# MyAmpV2.net
KiCad netlist of a schematic drawn in EAGLE
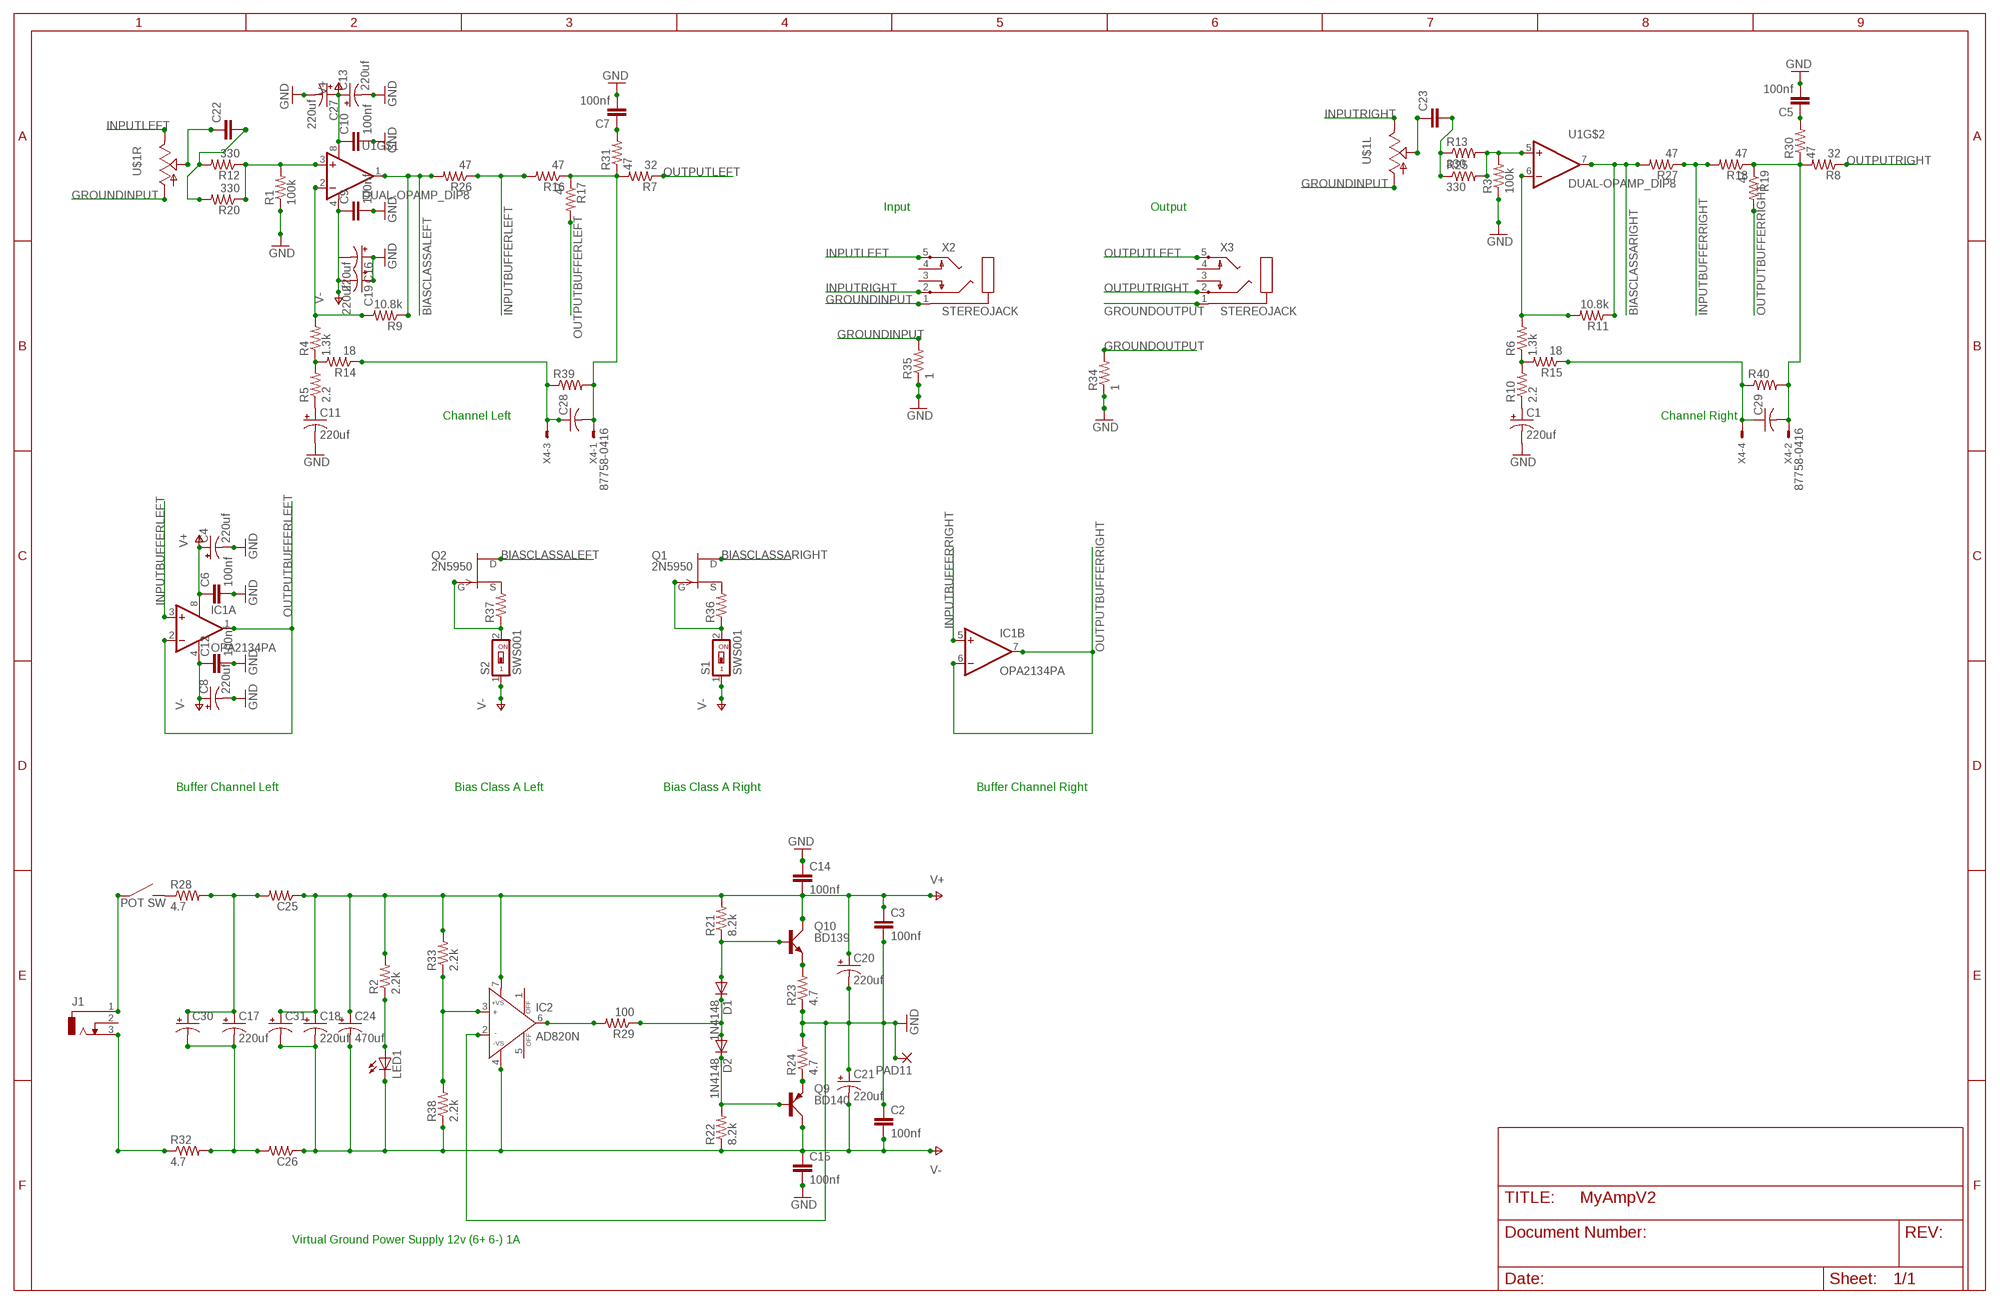
[diagram p0: schematic, sheet 1]

(export (version "E")
  (design (tool "Eeschema 10.0.6"))
  (components
    (comp (ref "C1")
      (value "220uf")
      (footprint "eagle-import:E5-10,5")
      (libsource (lib "eagle-import") (part "CPOL-USE5-10.5"))
    )
    (comp (ref "C2")
      (value "100nf")
      (footprint "eagle-import:C5B2.5")
      (libsource (lib "eagle-import") (part "C5/2.5"))
    )
    (comp (ref "C3")
      (value "100nf")
      (footprint "eagle-import:C5B2.5")
      (libsource (lib "eagle-import") (part "C5/2.5"))
    )
    (comp (ref "C4")
      (value "220uf")
      (footprint "eagle-import:E5-10,5")
      (libsource (lib "eagle-import") (part "CPOL-USE5-10.5"))
    )
    (comp (ref "C5")
      (value "100nf")
      (footprint "eagle-import:C5B2.5")
      (libsource (lib "eagle-import") (part "C5/2.5"))
    )
    (comp (ref "C6")
      (value "100nf")
      (footprint "eagle-import:C5B2.5")
      (libsource (lib "eagle-import") (part "C5/2.5"))
    )
    (comp (ref "C7")
      (value "100nf")
      (footprint "eagle-import:C5B2.5")
      (libsource (lib "eagle-import") (part "C5/2.5"))
    )
    (comp (ref "C8")
      (value "220uf")
      (footprint "eagle-import:E5-10,5")
      (libsource (lib "eagle-import") (part "CPOL-USE5-10.5"))
    )
    (comp (ref "C9")
      (value "100nf")
      (footprint "eagle-import:C5B2.5")
      (libsource (lib "eagle-import") (part "C5/2.5"))
    )
    (comp (ref "C10")
      (value "100nf")
      (footprint "eagle-import:C5B2.5")
      (libsource (lib "eagle-import") (part "C5/2.5"))
    )
    (comp (ref "C11")
      (value "220uf")
      (footprint "eagle-import:E5-10,5")
      (libsource (lib "eagle-import") (part "CPOL-USE5-10.5"))
    )
    (comp (ref "C12")
      (value "100nf")
      (footprint "eagle-import:C5B2.5")
      (libsource (lib "eagle-import") (part "C5/2.5"))
    )
    (comp (ref "C13")
      (value "220uf")
      (footprint "eagle-import:E5-10,5")
      (libsource (lib "eagle-import") (part "CPOL-USE5-10.5"))
    )
    (comp (ref "C14")
      (value "100nf")
      (footprint "eagle-import:C5B2.5")
      (libsource (lib "eagle-import") (part "C5/2.5"))
    )
    (comp (ref "C15")
      (value "100nf")
      (footprint "eagle-import:C5B2.5")
      (libsource (lib "eagle-import") (part "C5/2.5"))
    )
    (comp (ref "C16")
      (value "220uf")
      (footprint "eagle-import:E5-10,5")
      (libsource (lib "eagle-import") (part "CPOL-USE5-10.5"))
    )
    (comp (ref "C17")
      (value "220uf")
      (footprint "eagle-import:E5-10,5")
      (libsource (lib "eagle-import") (part "rcl_334_CPOL-USE5-10.5"))
    )
    (comp (ref "C18")
      (value "220uf")
      (footprint "eagle-import:E5-10,5")
      (libsource (lib "eagle-import") (part "rcl_334_CPOL-USE5-10.5"))
    )
    (comp (ref "C19")
      (value "220uf")
      (footprint "eagle-import:E5-10,5")
      (libsource (lib "eagle-import") (part "CPOL-USE5-10.5"))
    )
    (comp (ref "C20")
      (value "220uf")
      (footprint "eagle-import:D_7343-31R")
      (libsource (lib "eagle-import") (part "rcl_334_CPOL-USD/7343-31R"))
    )
    (comp (ref "C21")
      (value "220uf")
      (footprint "eagle-import:D_7343-31R")
      (libsource (lib "eagle-import") (part "rcl_334_CPOL-USD/7343-31R"))
    )
    (comp (ref "C22")
      (value "C22/6")
      (footprint "eagle-import:C22.5B6")
      (libsource (lib "eagle-import") (part "capacitor-wima_116_C22/6"))
    )
    (comp (ref "C23")
      (value "C22/6")
      (footprint "eagle-import:C22.5B6")
      (libsource (lib "eagle-import") (part "capacitor-wima_116_C22/6"))
    )
    (comp (ref "C24")
      (value "470uf")
      (footprint "eagle-import:E5-10,5")
      (libsource (lib "eagle-import") (part "CPOL-USE5-10.5"))
    )
    (comp (ref "C25")
      (value "R-US_0207/12")
      (footprint "eagle-import:0207_12")
      (libsource (lib "eagle-import") (part "resistor_348_R-US_0207/12"))
    )
    (comp (ref "C26")
      (value "R-US_0207/12")
      (footprint "eagle-import:0207_12")
      (libsource (lib "eagle-import") (part "resistor_348_R-US_0207/12"))
    )
    (comp (ref "C27")
      (value "220uf")
      (footprint "eagle-import:E5-10,5")
      (libsource (lib "eagle-import") (part "CPOL-USE5-10.5"))
    )
    (comp (ref "C28")
      (value "C-USC1206K")
      (footprint "eagle-import:C1206K")
      (libsource (lib "eagle-import") (part "C-USC1206K"))
    )
    (comp (ref "C29")
      (value "C-USC1206K")
      (footprint "eagle-import:C1206K")
      (libsource (lib "eagle-import") (part "C-USC1206K"))
    )
    (comp (ref "C30")
      (value "CPOL-USE7.5-16")
      (footprint "eagle-import:E7,5-16")
      (libsource (lib "eagle-import") (part "rcl_334_CPOL-USE7.5-16"))
    )
    (comp (ref "C31")
      (value "CPOL-USE7.5-16")
      (footprint "eagle-import:E7,5-16")
      (libsource (lib "eagle-import") (part "rcl_334_CPOL-USE7.5-16"))
    )
    (comp (ref "D1")
      (value "1N4148")
      (footprint "eagle-import:DO35-7")
      (libsource (lib "eagle-import") (part "1N4148DO35-7"))
    )
    (comp (ref "D2")
      (value "1N4148")
      (footprint "eagle-import:DO35-7")
      (libsource (lib "eagle-import") (part "1N4148DO35-7"))
    )
    (comp (ref "IC1")
      (value "OPA2134PA")
      (footprint "eagle-import:DIL08")
      (libsource (lib "eagle-import") (part "OPA2PA134"))
    )
    (comp (ref "IC2")
      (value "AD820N")
      (footprint "eagle-import:DIL08")
      (libsource (lib "eagle-import") (part "AD820N"))
    )
    (comp (ref "J1")
      (value "DCJ0303")
      (footprint "eagle-import:DCJ0303")
      (libsource (lib "eagle-import") (part "DCJ0303"))
    )
    (comp (ref "LED1")
      (value "LED3MM")
      (footprint "eagle-import:LED3MM")
      (libsource (lib "eagle-import") (part "LED3MM"))
    )
    (comp (ref "PAD11")
      (value "1,6/0,9")
      (footprint "eagle-import:1,6_0,9")
      (libsource (lib "eagle-import") (part "1,6/0,9"))
    )
    (comp (ref "Q1")
      (value "2N5950")
      (footprint "eagle-import:TO-92")
      (libsource (lib "eagle-import") (part "2N5950"))
    )
    (comp (ref "Q2")
      (value "2N5950")
      (footprint "eagle-import:TO-92")
      (libsource (lib "eagle-import") (part "2N5950"))
    )
    (comp (ref "Q9")
      (value "BD140")
      (footprint "eagle-import:TO126AV")
      (libsource (lib "eagle-import") (part "BD140"))
    )
    (comp (ref "Q10")
      (value "BD139")
      (footprint "eagle-import:TO126AV")
      (libsource (lib "eagle-import") (part "BD139"))
    )
    (comp (ref "R1")
      (value "100k")
      (footprint "eagle-import:0207_10")
      (libsource (lib "eagle-import") (part "R-US_0207/10"))
    )
    (comp (ref "R2")
      (value "2.2k")
      (footprint "eagle-import:0207_10")
      (libsource (lib "eagle-import") (part "resistor@1_R-US_0207/10"))
    )
    (comp (ref "R3")
      (value "100k")
      (footprint "eagle-import:0207_10")
      (libsource (lib "eagle-import") (part "R-US_0207/10"))
    )
    (comp (ref "R4")
      (value "1.3k")
      (footprint "eagle-import:0207_10")
      (libsource (lib "eagle-import") (part "R-US_0207/10"))
    )
    (comp (ref "R5")
      (value "2.2")
      (footprint "eagle-import:0204_5")
      (libsource (lib "eagle-import") (part "resistor_348_R-US_0204/5"))
    )
    (comp (ref "R6")
      (value "1.3k")
      (footprint "eagle-import:0207_10")
      (libsource (lib "eagle-import") (part "R-US_0207/10"))
    )
    (comp (ref "R7")
      (value "32")
      (footprint "eagle-import:0207_12")
      (libsource (lib "eagle-import") (part "resistor@1_R-US_0207/12"))
    )
    (comp (ref "R8")
      (value "32")
      (footprint "eagle-import:0207_12")
      (libsource (lib "eagle-import") (part "resistor@1_R-US_0207/12"))
    )
    (comp (ref "R9")
      (value "10.8k")
      (footprint "eagle-import:0207_10")
      (libsource (lib "eagle-import") (part "R-US_0207/10"))
    )
    (comp (ref "R10")
      (value "2.2")
      (footprint "eagle-import:0204_5")
      (libsource (lib "eagle-import") (part "resistor_348_R-US_0204/5"))
    )
    (comp (ref "R11")
      (value "10.8k")
      (footprint "eagle-import:0207_10")
      (libsource (lib "eagle-import") (part "R-US_0207/10"))
    )
    (comp (ref "R12")
      (value "330")
      (footprint "eagle-import:0207_10")
      (libsource (lib "eagle-import") (part "R-US_0207/10"))
    )
    (comp (ref "R13")
      (value "330")
      (footprint "eagle-import:0207_10")
      (libsource (lib "eagle-import") (part "R-US_0207/10"))
    )
    (comp (ref "R14")
      (value "18")
      (footprint "eagle-import:0207_12")
      (libsource (lib "eagle-import") (part "resistor@1_R-US_0207/12"))
    )
    (comp (ref "R15")
      (value "18")
      (footprint "eagle-import:0207_12")
      (libsource (lib "eagle-import") (part "resistor@1_R-US_0207/12"))
    )
    (comp (ref "R16")
      (value "47")
      (footprint "eagle-import:0207_12")
      (libsource (lib "eagle-import") (part "resistor@1_R-US_0207/12"))
    )
    (comp (ref "R17")
      (value "47")
      (footprint "eagle-import:0207_12")
      (libsource (lib "eagle-import") (part "resistor@1_R-US_0207/12"))
    )
    (comp (ref "R18")
      (value "47")
      (footprint "eagle-import:0207_12")
      (libsource (lib "eagle-import") (part "resistor@1_R-US_0207/12"))
    )
    (comp (ref "R19")
      (value "47")
      (footprint "eagle-import:0207_12")
      (libsource (lib "eagle-import") (part "resistor@1_R-US_0207/12"))
    )
    (comp (ref "R20")
      (value "330")
      (footprint "eagle-import:0207_10")
      (libsource (lib "eagle-import") (part "R-US_0207/10"))
    )
    (comp (ref "R21")
      (value "8.2k")
      (footprint "eagle-import:0207_10")
      (libsource (lib "eagle-import") (part "resistor@1_R-US_0207/10"))
    )
    (comp (ref "R22")
      (value "8.2k")
      (footprint "eagle-import:0207_10")
      (libsource (lib "eagle-import") (part "resistor@1_R-US_0207/10"))
    )
    (comp (ref "R23")
      (value "4.7")
      (footprint "eagle-import:0207_10")
      (libsource (lib "eagle-import") (part "resistor@1_R-US_0207/10"))
    )
    (comp (ref "R24")
      (value "4.7")
      (footprint "eagle-import:0207_10")
      (libsource (lib "eagle-import") (part "resistor@1_R-US_0207/10"))
    )
    (comp (ref "R25")
      (value "330")
      (footprint "eagle-import:0207_10")
      (libsource (lib "eagle-import") (part "R-US_0207/10"))
    )
    (comp (ref "R26")
      (value "47")
      (footprint "eagle-import:0207_10")
      (libsource (lib "eagle-import") (part "resistor@1_R-US_0207/10"))
    )
    (comp (ref "R27")
      (value "47")
      (footprint "eagle-import:0207_10")
      (libsource (lib "eagle-import") (part "resistor@1_R-US_0207/10"))
    )
    (comp (ref "R28")
      (value "4.7")
      (footprint "eagle-import:0207_10")
      (libsource (lib "eagle-import") (part "resistor@1_R-US_0207/10"))
    )
    (comp (ref "R29")
      (value "100")
      (footprint "eagle-import:0207_10")
      (libsource (lib "eagle-import") (part "resistor@1_R-US_0207/10"))
    )
    (comp (ref "R30")
      (value "47")
      (footprint "eagle-import:0207_7")
      (libsource (lib "eagle-import") (part "R-US_0207/7"))
    )
    (comp (ref "R31")
      (value "47")
      (footprint "eagle-import:0207_7")
      (libsource (lib "eagle-import") (part "R-US_0207/7"))
    )
    (comp (ref "R32")
      (value "4.7")
      (footprint "eagle-import:0207_10")
      (libsource (lib "eagle-import") (part "resistor@1_R-US_0207/10"))
    )
    (comp (ref "R33")
      (value "2.2k")
      (footprint "eagle-import:0207_10")
      (libsource (lib "eagle-import") (part "resistor@1_R-US_0207/10"))
    )
    (comp (ref "R34")
      (value "1")
      (footprint "eagle-import:0207_7")
      (libsource (lib "eagle-import") (part "R-US_0207/7"))
    )
    (comp (ref "R35")
      (value "1")
      (footprint "eagle-import:0207_7")
      (libsource (lib "eagle-import") (part "R-US_0207/7"))
    )
    (comp (ref "R36")
      (value "R-US_0204/5")
      (footprint "eagle-import:0204_5")
      (libsource (lib "eagle-import") (part "resistor@1_R-US_0204/5"))
    )
    (comp (ref "R37")
      (value "R-US_0204/5")
      (footprint "eagle-import:0204_5")
      (libsource (lib "eagle-import") (part "resistor@1_R-US_0204/5"))
    )
    (comp (ref "R38")
      (value "2.2k")
      (footprint "eagle-import:0207_10")
      (libsource (lib "eagle-import") (part "resistor@1_R-US_0207/10"))
    )
    (comp (ref "R39")
      (value "R-US_MELF0204W")
      (footprint "eagle-import:MINI_MELF-0204W")
      (libsource (lib "eagle-import") (part "resistor_348_R-US_MELF0204W"))
    )
    (comp (ref "R40")
      (value "R-US_MELF0204W")
      (footprint "eagle-import:MINI_MELF-0204W")
      (libsource (lib "eagle-import") (part "resistor_348_R-US_MELF0204W"))
    )
    (comp (ref "S1")
      (value "SWS001")
      (footprint "eagle-import:SMS-001")
      (libsource (lib "eagle-import") (part "SWS001"))
    )
    (comp (ref "S2")
      (value "SWS001")
      (footprint "eagle-import:SMS-001")
      (libsource (lib "eagle-import") (part "SWS001"))
    )
    (comp (ref "U$1")
      (value "ALPS_RK0971221Z05")
      (footprint "eagle-import:ALPS_RK0971221Z0X")
      (libsource (lib "eagle-import") (part "ALPS_RK0971221Z05"))
    )
    (comp (ref "U1")
      (value "DUAL-OPAMP_DIP8")
      (footprint "eagle-import:DIP-8")
      (libsource (lib "eagle-import") (part "DUAL-OPAMP_DIP8"))
    )
    (comp (ref "X2")
      (value "STEREOJACK")
      (footprint "eagle-import:STX3100")
      (libsource (lib "eagle-import") (part "STEREOJACK"))
    )
    (comp (ref "X3")
      (value "STEREOJACK")
      (footprint "eagle-import:STX3100")
      (libsource (lib "eagle-import") (part "STEREOJACK"))
    )
    (comp (ref "X4")
      (value "87758-0416")
      (footprint "eagle-import:87758-0416")
      (fields (field (name "MF") "FARNELL"))
      (libsource (lib "eagle-import") (part "87758-0416"))
    )
  )
  (nets
    (net (code "1") (name "/BIASCLASSALEFT") (class "Default")
      (node (ref "Q2") (pin "3") (pinfunction "D_3") (pintype "passive"))
      (node (ref "R26") (pin "2") (pinfunction "2_2") (pintype "passive"))
      (node (ref "R9") (pin "1") (pinfunction "1_1") (pintype "passive"))
      (node (ref "U1") (pin "1") (pinfunction "OUT_1") (pintype "output"))
    )
    (net (code "2") (name "/BIASCLASSARIGHT") (class "Default")
      (node (ref "Q1") (pin "3") (pinfunction "D_3") (pintype "passive"))
      (node (ref "R11") (pin "1") (pinfunction "1_1") (pintype "passive"))
      (node (ref "R27") (pin "2") (pinfunction "2_2") (pintype "passive"))
      (node (ref "U1") (pin "7") (pinfunction "OUT_7") (pintype "output"))
    )
    (net (code "3") (name "/GROUNDINPUT") (class "Default")
      (node (ref "R35") (pin "2") (pinfunction "2_2") (pintype "passive"))
      (node (ref "U$1") (pin "G1") (pinfunction "1_G1") (pintype "passive"))
      (node (ref "U$1") (pin "G2") (pinfunction "1_G2") (pintype "passive"))
      (node (ref "X2") (pin "1") (pinfunction "1_1") (pintype "passive"))
    )
    (net (code "4") (name "/GROUNDOUTPUT") (class "Default")
      (node (ref "R34") (pin "2") (pinfunction "2_2") (pintype "passive"))
      (node (ref "X3") (pin "1") (pinfunction "1_1") (pintype "passive"))
    )
    (net (code "5") (name "/INPUTBUFFERLEFT") (class "Default")
      (node (ref "IC1") (pin "3") (pinfunction "+IN_3") (pintype "input"))
      (node (ref "R16") (pin "2") (pinfunction "2_2") (pintype "passive"))
      (node (ref "R26") (pin "1") (pinfunction "1_1") (pintype "passive"))
    )
    (net (code "6") (name "/INPUTBUFFERRIGHT") (class "Default")
      (node (ref "IC1") (pin "5") (pinfunction "+IN_5") (pintype "input"))
      (node (ref "R18") (pin "2") (pinfunction "2_2") (pintype "passive"))
      (node (ref "R27") (pin "1") (pinfunction "1_1") (pintype "passive"))
    )
    (net (code "7") (name "/INPUTLEFT") (class "Default")
      (node (ref "U$1") (pin "I2") (pinfunction "3_I2") (pintype "passive"))
      (node (ref "X2") (pin "5") (pinfunction "5_5") (pintype "passive"))
    )
    (net (code "8") (name "/INPUTRIGHT") (class "Default")
      (node (ref "U$1") (pin "I1") (pinfunction "3_I1") (pintype "passive"))
      (node (ref "X2") (pin "2") (pinfunction "2_2") (pintype "passive"))
    )
    (net (code "9") (name "/OUTPUTBUFFERLEFT") (class "Default")
      (node (ref "IC1") (pin "1") (pinfunction "OUT_1") (pintype "output"))
      (node (ref "IC1") (pin "2") (pinfunction "-IN_2") (pintype "input"))
      (node (ref "R17") (pin "2") (pinfunction "2_2") (pintype "passive"))
    )
    (net (code "10") (name "/OUTPUTBUFFERRIGHT") (class "Default")
      (node (ref "IC1") (pin "6") (pinfunction "-IN_6") (pintype "input"))
      (node (ref "IC1") (pin "7") (pinfunction "OUT_7") (pintype "output"))
      (node (ref "R19") (pin "2") (pinfunction "2_2") (pintype "passive"))
    )
    (net (code "11") (name "/OUTPUTLEFT") (class "Default")
      (node (ref "R7") (pin "1") (pinfunction "1_1") (pintype "passive"))
      (node (ref "X3") (pin "5") (pinfunction "5_5") (pintype "passive"))
    )
    (net (code "12") (name "/OUTPUTRIGHT") (class "Default")
      (node (ref "R8") (pin "1") (pinfunction "1_1") (pintype "passive"))
      (node (ref "X3") (pin "2") (pinfunction "2_2") (pintype "passive"))
    )
    (net (code "13") (name "GND") (class "Default")
      (node (ref "C1") (pin "-") (pinfunction "-_-") (pintype "passive"))
      (node (ref "C10") (pin "2") (pinfunction "2_2") (pintype "passive"))
      (node (ref "C11") (pin "-") (pinfunction "-_-") (pintype "passive"))
      (node (ref "C12") (pin "2") (pinfunction "2_2") (pintype "passive"))
      (node (ref "C13") (pin "-") (pinfunction "-_-") (pintype "passive"))
      (node (ref "C14") (pin "1") (pinfunction "1_1") (pintype "passive"))
      (node (ref "C15") (pin "2") (pinfunction "2_2") (pintype "passive"))
      (node (ref "C16") (pin "+") (pinfunction "+_+") (pintype "passive"))
      (node (ref "C19") (pin "+") (pinfunction "+_+") (pintype "passive"))
      (node (ref "C2") (pin "1") (pinfunction "1_1") (pintype "passive"))
      (node (ref "C20") (pin "-") (pinfunction "-_-") (pintype "passive"))
      (node (ref "C21") (pin "+") (pinfunction "+_+") (pintype "passive"))
      (node (ref "C27") (pin "-") (pinfunction "-_-") (pintype "passive"))
      (node (ref "C3") (pin "2") (pinfunction "2_2") (pintype "passive"))
      (node (ref "C4") (pin "-") (pinfunction "-_-") (pintype "passive"))
      (node (ref "C5") (pin "2") (pinfunction "2_2") (pintype "passive"))
      (node (ref "C6") (pin "2") (pinfunction "2_2") (pintype "passive"))
      (node (ref "C7") (pin "2") (pinfunction "2_2") (pintype "passive"))
      (node (ref "C8") (pin "-") (pinfunction "-_-") (pintype "passive"))
      (node (ref "C9") (pin "2") (pinfunction "2_2") (pintype "passive"))
      (node (ref "IC2") (pin "2") (pinfunction "IN-_2") (pintype "input"))
      (node (ref "PAD11") (pin "1") (pinfunction "P_1") (pintype "passive"))
      (node (ref "R1") (pin "1") (pinfunction "1_1") (pintype "passive"))
      (node (ref "R23") (pin "1") (pinfunction "1_1") (pintype "passive"))
      (node (ref "R24") (pin "2") (pinfunction "2_2") (pintype "passive"))
      (node (ref "R3") (pin "1") (pinfunction "1_1") (pintype "passive"))
      (node (ref "R34") (pin "1") (pinfunction "1_1") (pintype "passive"))
      (node (ref "R35") (pin "1") (pinfunction "1_1") (pintype "passive"))
    )
    (net (code "14") (name "Net-(C1-Pad+)") (class "Default")
      (node (ref "C1") (pin "+") (pinfunction "+_+") (pintype "passive"))
      (node (ref "R10") (pin "1") (pinfunction "1_1") (pintype "passive"))
    )
    (net (code "15") (name "Net-(C5-Pad1)") (class "Default")
      (node (ref "C5") (pin "1") (pinfunction "1_1") (pintype "passive"))
      (node (ref "R30") (pin "2") (pinfunction "2_2") (pintype "passive"))
    )
    (net (code "16") (name "Net-(C7-Pad1)") (class "Default")
      (node (ref "C7") (pin "1") (pinfunction "1_1") (pintype "passive"))
      (node (ref "R31") (pin "2") (pinfunction "2_2") (pintype "passive"))
    )
    (net (code "17") (name "Net-(C11-Pad+)") (class "Default")
      (node (ref "C11") (pin "+") (pinfunction "+_+") (pintype "passive"))
      (node (ref "R5") (pin "1") (pinfunction "1_1") (pintype "passive"))
    )
    (net (code "18") (name "Net-(C17-Pad+)") (class "Default")
      (node (ref "C17") (pin "+") (pinfunction "+_+") (pintype "passive"))
      (node (ref "C25") (pin "2") (pinfunction "2_2") (pintype "passive"))
      (node (ref "C30") (pin "+") (pinfunction "+_+") (pintype "passive"))
      (node (ref "R28") (pin "2") (pinfunction "2_2") (pintype "passive"))
    )
    (net (code "19") (name "Net-(C17-Pad-)") (class "Default")
      (node (ref "C17") (pin "-") (pinfunction "-_-") (pintype "passive"))
      (node (ref "C26") (pin "2") (pinfunction "2_2") (pintype "passive"))
      (node (ref "C30") (pin "-") (pinfunction "-_-") (pintype "passive"))
      (node (ref "R32") (pin "2") (pinfunction "2_2") (pintype "passive"))
    )
    (net (code "20") (name "Net-(C22-Pad2)") (class "Default")
      (node (ref "C22") (pin "2") (pinfunction "2_2") (pintype "passive"))
      (node (ref "R12") (pin "2") (pinfunction "2_2") (pintype "passive"))
      (node (ref "R20") (pin "2") (pinfunction "2_2") (pintype "passive"))
    )
    (net (code "21") (name "Net-(C23-Pad2)") (class "Default")
      (node (ref "C23") (pin "2") (pinfunction "2_2") (pintype "passive"))
      (node (ref "R13") (pin "1") (pinfunction "1_1") (pintype "passive"))
      (node (ref "R25") (pin "1") (pinfunction "1_1") (pintype "passive"))
    )
    (net (code "22") (name "Net-(D1-PadA)") (class "Default")
      (node (ref "D1") (pin "A") (pinfunction "A_A") (pintype "passive"))
      (node (ref "Q10") (pin "B") (pinfunction "B_B") (pintype "passive"))
      (node (ref "R21") (pin "1") (pinfunction "1_1") (pintype "passive"))
    )
    (net (code "23") (name "Net-(D1-PadC)") (class "Default")
      (node (ref "D1") (pin "C") (pinfunction "C_C") (pintype "passive"))
      (node (ref "D2") (pin "A") (pinfunction "A_A") (pintype "passive"))
      (node (ref "R29") (pin "1") (pinfunction "1_1") (pintype "passive"))
    )
    (net (code "24") (name "Net-(D2-PadC)") (class "Default")
      (node (ref "D2") (pin "C") (pinfunction "C_C") (pintype "passive"))
      (node (ref "Q9") (pin "B") (pinfunction "B_B") (pintype "passive"))
      (node (ref "R22") (pin "2") (pinfunction "2_2") (pintype "passive"))
    )
    (net (code "25") (name "Net-(IC2-IN+)") (class "Default")
      (node (ref "IC2") (pin "3") (pinfunction "IN+_3") (pintype "input"))
      (node (ref "R33") (pin "1") (pinfunction "1_1") (pintype "passive"))
      (node (ref "R38") (pin "2") (pinfunction "2_2") (pintype "passive"))
    )
    (net (code "26") (name "Net-(IC2-OUT)") (class "Default")
      (node (ref "IC2") (pin "6") (pinfunction "OUT_6") (pintype "output"))
      (node (ref "R29") (pin "2") (pinfunction "2_2") (pintype "passive"))
    )
    (net (code "27") (name "Net-(J1-Pad1)") (class "Default")
      (node (ref "J1") (pin "1") (pinfunction "1_1") (pintype "passive"))
      (node (ref "U$1") (pin "S1") (pinfunction "S1_S1") (pintype "power_in"))
    )
    (net (code "28") (name "Net-(J1-Pad3)") (class "Default")
      (node (ref "J1") (pin "3") (pinfunction "3_3") (pintype "passive"))
      (node (ref "R32") (pin "1") (pinfunction "1_1") (pintype "passive"))
    )
    (net (code "29") (name "Net-(LED1-PadA)") (class "Default")
      (node (ref "LED1") (pin "A") (pinfunction "A_A") (pintype "passive"))
      (node (ref "R2") (pin "1") (pinfunction "1_1") (pintype "passive"))
    )
    (net (code "30") (name "Net-(Q1-G)") (class "Default")
      (node (ref "Q1") (pin "1") (pinfunction "G_1") (pintype "passive"))
      (node (ref "R36") (pin "1") (pinfunction "1_1") (pintype "passive"))
      (node (ref "S1") (pin "2") (pinfunction "2_2") (pintype "passive"))
    )
    (net (code "31") (name "Net-(Q1-S)") (class "Default")
      (node (ref "Q1") (pin "2") (pinfunction "S_2") (pintype "passive"))
      (node (ref "R36") (pin "2") (pinfunction "2_2") (pintype "passive"))
    )
    (net (code "32") (name "Net-(Q2-G)") (class "Default")
      (node (ref "Q2") (pin "1") (pinfunction "G_1") (pintype "passive"))
      (node (ref "R37") (pin "1") (pinfunction "1_1") (pintype "passive"))
      (node (ref "S2") (pin "2") (pinfunction "2_2") (pintype "passive"))
    )
    (net (code "33") (name "Net-(Q2-S)") (class "Default")
      (node (ref "Q2") (pin "2") (pinfunction "S_2") (pintype "passive"))
      (node (ref "R37") (pin "2") (pinfunction "2_2") (pintype "passive"))
    )
    (net (code "34") (name "Net-(Q9-PadE)") (class "Default")
      (node (ref "Q9") (pin "E") (pinfunction "E_E") (pintype "passive"))
      (node (ref "R24") (pin "1") (pinfunction "1_1") (pintype "passive"))
    )
    (net (code "35") (name "Net-(Q10-PadE)") (class "Default")
      (node (ref "Q10") (pin "E") (pinfunction "E_E") (pintype "passive"))
      (node (ref "R23") (pin "2") (pinfunction "2_2") (pintype "passive"))
    )
    (net (code "36") (name "Net-(R10-Pad2)") (class "Default")
      (node (ref "R10") (pin "2") (pinfunction "2_2") (pintype "passive"))
      (node (ref "R15") (pin "2") (pinfunction "2_2") (pintype "passive"))
      (node (ref "R6") (pin "1") (pinfunction "1_1") (pintype "passive"))
    )
    (net (code "37") (name "Net-(R14-Pad2)") (class "Default")
      (node (ref "R14") (pin "2") (pinfunction "2_2") (pintype "passive"))
      (node (ref "R4") (pin "1") (pinfunction "1_1") (pintype "passive"))
      (node (ref "R5") (pin "2") (pinfunction "2_2") (pintype "passive"))
    )
    (net (code "38") (name "Net-(R28-Pad1)") (class "Default")
      (node (ref "R28") (pin "1") (pinfunction "1_1") (pintype "passive"))
      (node (ref "U$1") (pin "S2") (pinfunction "S2_S2") (pintype "power_in"))
    )
    (net (code "39") (name "Net-(U$1B-2)") (class "Default")
      (node (ref "C23") (pin "1") (pinfunction "1_1") (pintype "passive"))
      (node (ref "U$1") (pin "O1") (pinfunction "2_O1") (pintype "passive"))
    )
    (net (code "40") (name "Net-(U$1C-2)") (class "Default")
      (node (ref "C22") (pin "1") (pinfunction "1_1") (pintype "passive"))
      (node (ref "U$1") (pin "O2") (pinfunction "2_O2") (pintype "passive"))
    )
    (net (code "41") (name "Net-(U1A-+IN)") (class "Default")
      (node (ref "R1") (pin "2") (pinfunction "2_2") (pintype "passive"))
      (node (ref "R12") (pin "1") (pinfunction "1_1") (pintype "passive"))
      (node (ref "R20") (pin "1") (pinfunction "1_1") (pintype "passive"))
      (node (ref "U1") (pin "3") (pinfunction "+IN_3") (pintype "input"))
    )
    (net (code "42") (name "Net-(U1A--IN)") (class "Default")
      (node (ref "R4") (pin "2") (pinfunction "2_2") (pintype "passive"))
      (node (ref "R9") (pin "2") (pinfunction "2_2") (pintype "passive"))
      (node (ref "U1") (pin "2") (pinfunction "-IN_2") (pintype "input"))
    )
    (net (code "43") (name "Net-(U1B-+IN)") (class "Default")
      (node (ref "R13") (pin "2") (pinfunction "2_2") (pintype "passive"))
      (node (ref "R25") (pin "2") (pinfunction "2_2") (pintype "passive"))
      (node (ref "R3") (pin "2") (pinfunction "2_2") (pintype "passive"))
      (node (ref "U1") (pin "5") (pinfunction "+IN_5") (pintype "input"))
    )
    (net (code "44") (name "Net-(U1B--IN)") (class "Default")
      (node (ref "R11") (pin "2") (pinfunction "2_2") (pintype "passive"))
      (node (ref "R6") (pin "2") (pinfunction "2_2") (pintype "passive"))
      (node (ref "U1") (pin "6") (pinfunction "-IN_6") (pintype "input"))
    )
    (net (code "45") (name "Net-(X4A-S)") (class "Default")
      (node (ref "C28") (pin "2") (pinfunction "2_2") (pintype "passive"))
      (node (ref "R16") (pin "1") (pinfunction "1_1") (pintype "passive"))
      (node (ref "R17") (pin "1") (pinfunction "1_1") (pintype "passive"))
      (node (ref "R31") (pin "1") (pinfunction "1_1") (pintype "passive"))
      (node (ref "R39") (pin "2") (pinfunction "2_2") (pintype "passive"))
      (node (ref "R7") (pin "2") (pinfunction "2_2") (pintype "passive"))
      (node (ref "X4") (pin "1") (pinfunction "S_1") (pintype "passive"))
    )
    (net (code "46") (name "Net-(X4B-S)") (class "Default")
      (node (ref "C29") (pin "2") (pinfunction "2_2") (pintype "passive"))
      (node (ref "R18") (pin "1") (pinfunction "1_1") (pintype "passive"))
      (node (ref "R19") (pin "1") (pinfunction "1_1") (pintype "passive"))
      (node (ref "R30") (pin "1") (pinfunction "1_1") (pintype "passive"))
      (node (ref "R40") (pin "2") (pinfunction "2_2") (pintype "passive"))
      (node (ref "R8") (pin "2") (pinfunction "2_2") (pintype "passive"))
      (node (ref "X4") (pin "2") (pinfunction "S_2") (pintype "passive"))
    )
    (net (code "47") (name "Net-(X4C-S)") (class "Default")
      (node (ref "C28") (pin "1") (pinfunction "1_1") (pintype "passive"))
      (node (ref "R14") (pin "1") (pinfunction "1_1") (pintype "passive"))
      (node (ref "R39") (pin "1") (pinfunction "1_1") (pintype "passive"))
      (node (ref "X4") (pin "3") (pinfunction "S_3") (pintype "passive"))
    )
    (net (code "48") (name "Net-(X4D-S)") (class "Default")
      (node (ref "C29") (pin "1") (pinfunction "1_1") (pintype "passive"))
      (node (ref "R15") (pin "1") (pinfunction "1_1") (pintype "passive"))
      (node (ref "R40") (pin "1") (pinfunction "1_1") (pintype "passive"))
      (node (ref "X4") (pin "4") (pinfunction "S_4") (pintype "passive"))
    )
    (net (code "49") (name "V+") (class "Default")
      (node (ref "C10") (pin "1") (pinfunction "1_1") (pintype "passive"))
      (node (ref "C13") (pin "+") (pinfunction "+_+") (pintype "passive"))
      (node (ref "C14") (pin "2") (pinfunction "2_2") (pintype "passive"))
      (node (ref "C18") (pin "+") (pinfunction "+_+") (pintype "passive"))
      (node (ref "C20") (pin "+") (pinfunction "+_+") (pintype "passive"))
      (node (ref "C24") (pin "+") (pinfunction "+_+") (pintype "passive"))
      (node (ref "C25") (pin "1") (pinfunction "1_1") (pintype "passive"))
      (node (ref "C27") (pin "+") (pinfunction "+_+") (pintype "passive"))
      (node (ref "C3") (pin "1") (pinfunction "1_1") (pintype "passive"))
      (node (ref "C31") (pin "+") (pinfunction "+_+") (pintype "passive"))
      (node (ref "C4") (pin "+") (pinfunction "+_+") (pintype "passive"))
      (node (ref "C6") (pin "1") (pinfunction "1_1") (pintype "passive"))
      (node (ref "IC1") (pin "8") (pinfunction "V+_8") (pintype "power_in"))
      (node (ref "IC2") (pin "7") (pinfunction "+VS_7") (pintype "input"))
      (node (ref "Q10") (pin "C") (pinfunction "C_C") (pintype "passive"))
      (node (ref "R2") (pin "2") (pinfunction "2_2") (pintype "passive"))
      (node (ref "R21") (pin "2") (pinfunction "2_2") (pintype "passive"))
      (node (ref "R33") (pin "2") (pinfunction "2_2") (pintype "passive"))
      (node (ref "U1") (pin "8") (pinfunction "V+_8") (pintype "power_in"))
    )
    (net (code "50") (name "V-") (class "Default")
      (node (ref "C12") (pin "1") (pinfunction "1_1") (pintype "passive"))
      (node (ref "C15") (pin "1") (pinfunction "1_1") (pintype "passive"))
      (node (ref "C16") (pin "-") (pinfunction "-_-") (pintype "passive"))
      (node (ref "C18") (pin "-") (pinfunction "-_-") (pintype "passive"))
      (node (ref "C19") (pin "-") (pinfunction "-_-") (pintype "passive"))
      (node (ref "C2") (pin "2") (pinfunction "2_2") (pintype "passive"))
      (node (ref "C21") (pin "-") (pinfunction "-_-") (pintype "passive"))
      (node (ref "C24") (pin "-") (pinfunction "-_-") (pintype "passive"))
      (node (ref "C26") (pin "1") (pinfunction "1_1") (pintype "passive"))
      (node (ref "C31") (pin "-") (pinfunction "-_-") (pintype "passive"))
      (node (ref "C8") (pin "+") (pinfunction "+_+") (pintype "passive"))
      (node (ref "C9") (pin "1") (pinfunction "1_1") (pintype "passive"))
      (node (ref "IC1") (pin "4") (pinfunction "V-_4") (pintype "power_in"))
      (node (ref "IC2") (pin "4") (pinfunction "-VS_4") (pintype "input"))
      (node (ref "LED1") (pin "K") (pinfunction "C_K") (pintype "passive"))
      (node (ref "Q9") (pin "C") (pinfunction "C_C") (pintype "passive"))
      (node (ref "R22") (pin "1") (pinfunction "1_1") (pintype "passive"))
      (node (ref "R38") (pin "1") (pinfunction "1_1") (pintype "passive"))
      (node (ref "S1") (pin "1") (pinfunction "1_1") (pintype "passive"))
      (node (ref "S2") (pin "1") (pinfunction "1_1") (pintype "passive"))
      (node (ref "U1") (pin "4") (pinfunction "V-_4") (pintype "power_in"))
    )
    (net (code "51") (name "unconnected-(IC2-OFF-Pad1)") (class "Default")
      (node (ref "IC2") (pin "1") (pinfunction "OFF_1") (pintype "passive"))
    )
    (net (code "52") (name "unconnected-(IC2-OFF-Pad5)") (class "Default")
      (node (ref "IC2") (pin "5") (pinfunction "OFF_5") (pintype "passive"))
    )
    (net (code "53") (name "unconnected-(J1-Pad2)") (class "Default")
      (node (ref "J1") (pin "2") (pinfunction "2_2") (pintype "passive"))
    )
    (net (code "54") (name "unconnected-(X2-Pad3)") (class "Default")
      (node (ref "X2") (pin "3") (pinfunction "3_3") (pintype "passive"))
    )
    (net (code "55") (name "unconnected-(X2-Pad4)") (class "Default")
      (node (ref "X2") (pin "4") (pinfunction "4_4") (pintype "passive"))
    )
    (net (code "56") (name "unconnected-(X3-Pad3)") (class "Default")
      (node (ref "X3") (pin "3") (pinfunction "3_3") (pintype "passive"))
    )
    (net (code "57") (name "unconnected-(X3-Pad4)") (class "Default")
      (node (ref "X3") (pin "4") (pinfunction "4_4") (pintype "passive"))
    )
  )
)
